# energymetter_labsi.net
KiCad netlist of a schematic drawn in EAGLE
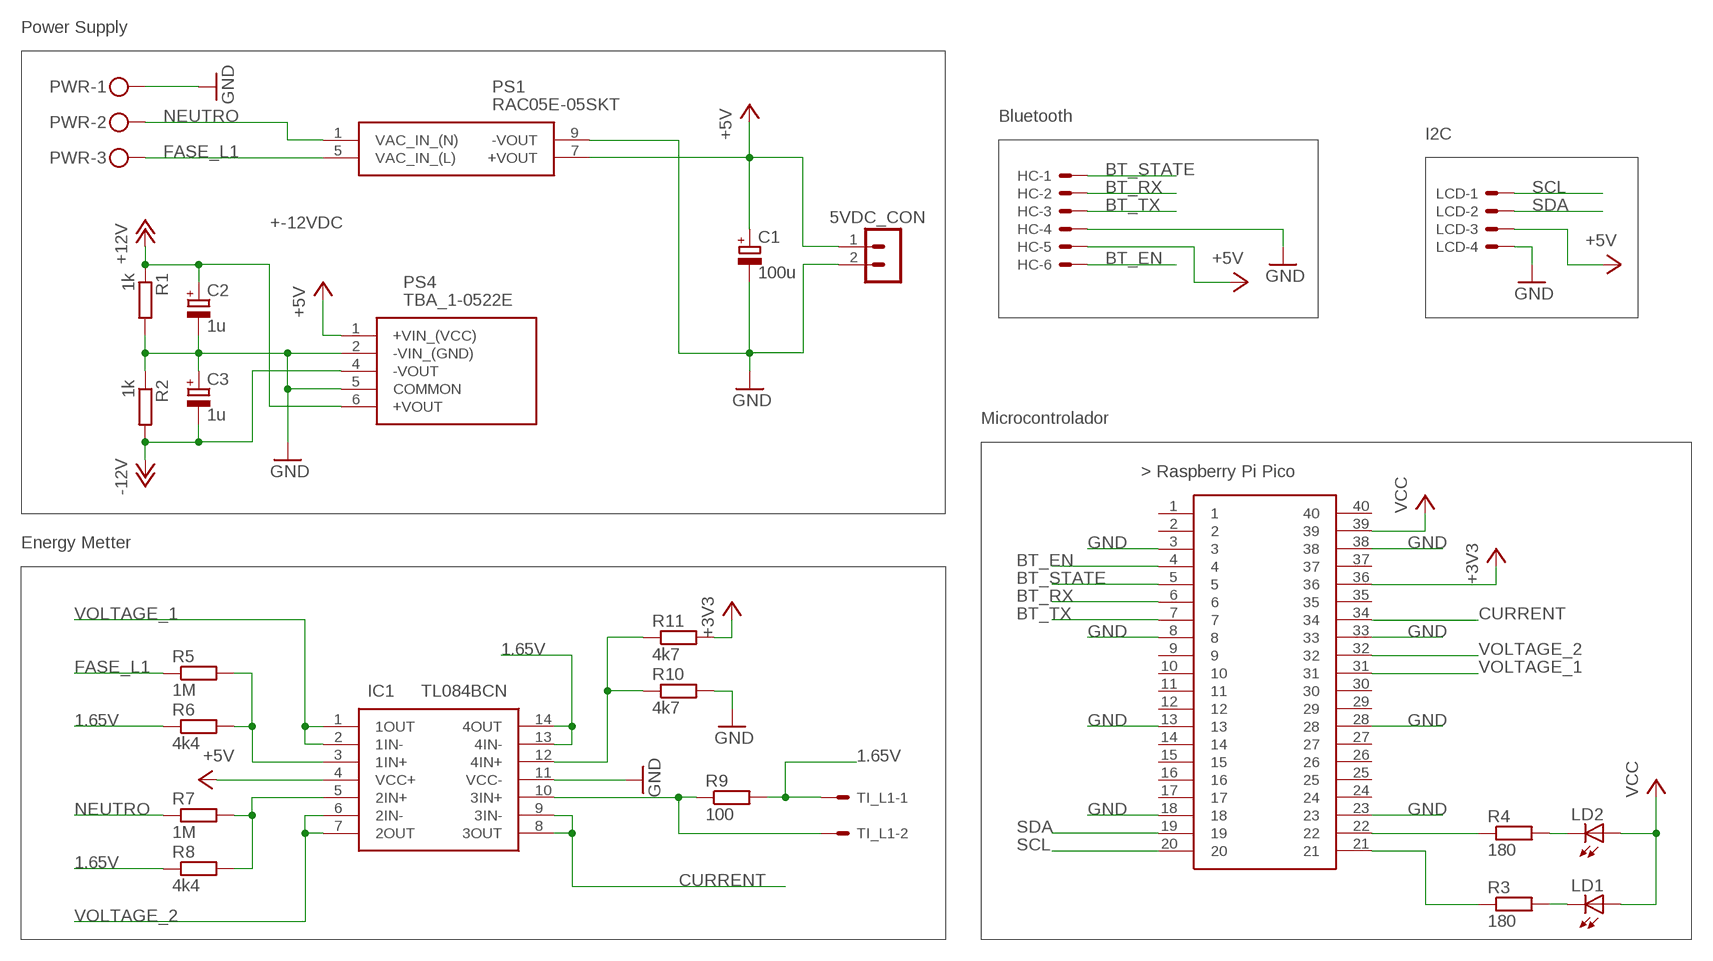
[diagram p0: schematic, sheet 1]

(export (version "E")
  (design (tool "Eeschema 10.0.6"))
  (components
    (comp (ref "5VDC_CON")
      (value "MA02-1")
      (footprint "eagle-import:MA02-1")
      (libsource (lib "eagle-import") (part "MA02-1"))
    )
    (comp (ref "C1")
      (value "100u")
      (footprint "eagle-import:E2-5")
      (libsource (lib "eagle-import") (part "CPOL-EUE2-5"))
    )
    (comp (ref "C2")
      (value "1u")
      (footprint "eagle-import:E2-5")
      (libsource (lib "eagle-import") (part "CPOL-EUE2-5"))
    )
    (comp (ref "C3")
      (value "1u")
      (footprint "eagle-import:E2-5")
      (libsource (lib "eagle-import") (part "CPOL-EUE2-5"))
    )
    (comp (ref "HC")
      (value "22-23-2061")
      (footprint "eagle-import:22-23-2061")
      (fields (field (name "MF") "MOLEX"))
      (libsource (lib "eagle-import") (part "22-23-2061"))
    )
    (comp (ref "IC1")
      (value "TL084BCN")
      (footprint "eagle-import:DIP794W53P254L1930H508Q14N")
      (fields (field (name "MOUSER_PART_NUMBER") "595-TL084BCN"))
      (libsource (lib "eagle-import") (part "TL084BCN"))
    )
    (comp (ref "LCD")
      (value "Display")
      (footprint "eagle-import:22-23-2041")
      (fields (field (name "MF") "MOLEX") (field (name "MPN") "22-23-2041"))
      (libsource (lib "eagle-import") (part "22-23-2041"))
    )
    (comp (ref "LD1")
      (value "LED5MM")
      (footprint "eagle-import:LED5MM")
      (libsource (lib "eagle-import") (part "LED5MM"))
    )
    (comp (ref "LD2")
      (value "LED5MM")
      (footprint "eagle-import:LED5MM")
      (libsource (lib "eagle-import") (part "LED5MM"))
    )
    (comp (ref "PS1")
      (value "RAC05E-05SKT")
      (footprint "eagle-import:RAC05E05SKT")
      (fields (field (name "MOUSER_PART_NUMBER") "919-RAC05E-05SKT"))
      (libsource (lib "eagle-import") (part "RAC05E-05SKT"))
    )
    (comp (ref "PS4")
      (value "TBA_1-0522E")
      (footprint "eagle-import:TBA10522E")
      (fields
        (field (name "MANUFACTURER_PART_NUMBER") "TBA 1-0522E")
        (field (name "MOUSER_PART_NUMBER") "495-TBA1-0522E")
      )
      (libsource (lib "eagle-import") (part "TBA_1-0522E"))
    )
    (comp (ref "PWR")
      (value "MKDSN1,5/3-5,08")
      (footprint "eagle-import:MKDSN1,5_3-5,08")
      (libsource (lib "eagle-import") (part "MKDSN1,5/3-5,08"))
    )
    (comp (ref "R1")
      (value "1k")
      (footprint "eagle-import:0204_7")
      (libsource (lib "eagle-import") (part "R-EU_0204/7"))
    )
    (comp (ref "R2")
      (value "1k")
      (footprint "eagle-import:0204_7")
      (libsource (lib "eagle-import") (part "R-EU_0204/7"))
    )
    (comp (ref "R3")
      (value "180")
      (footprint "eagle-import:0204_7")
      (libsource (lib "eagle-import") (part "R-EU_0204/7"))
    )
    (comp (ref "R4")
      (value "180")
      (footprint "eagle-import:0204_7")
      (libsource (lib "eagle-import") (part "R-EU_0204/7"))
    )
    (comp (ref "R5")
      (value "1M")
      (footprint "eagle-import:0204_7")
      (libsource (lib "eagle-import") (part "R-EU_0204/7"))
    )
    (comp (ref "R6")
      (value "4k4")
      (footprint "eagle-import:0204_7")
      (libsource (lib "eagle-import") (part "R-EU_0204/7"))
    )
    (comp (ref "R7")
      (value "1M")
      (footprint "eagle-import:0204_7")
      (libsource (lib "eagle-import") (part "R-EU_0204/7"))
    )
    (comp (ref "R8")
      (value "4k4")
      (footprint "eagle-import:0204_7")
      (libsource (lib "eagle-import") (part "R-EU_0204/7"))
    )
    (comp (ref "R9")
      (value "100")
      (footprint "eagle-import:0204_7")
      (libsource (lib "eagle-import") (part "R-EU_0204/7"))
    )
    (comp (ref "R10")
      (value "4k7")
      (footprint "eagle-import:0204_7")
      (libsource (lib "eagle-import") (part "R-EU_0204/7"))
    )
    (comp (ref "R11")
      (value "4k7")
      (footprint "eagle-import:0204_7")
      (libsource (lib "eagle-import") (part "R-EU_0204/7"))
    )
    (comp (ref "TI_L1")
      (value "22-23-2021")
      (footprint "eagle-import:22-23-2021")
      (fields (field (name "MF") "MOLEX"))
      (libsource (lib "eagle-import") (part "22-23-2021"))
    )
    (comp (ref "U$1")
      (value "RASPBERRY-PI-PICO_TH")
      (footprint "eagle-import:FT_RASPBERRY-PI-PICO_TH")
      (libsource (lib "eagle-import") (part "RASPBERRY-PI-PICO_TH"))
    )
  )
  (nets
    (net (code "1") (name "+3V3") (class "Default")
      (node (ref "R11") (pin "2") (pinfunction "2_2") (pintype "passive"))
      (node (ref "U$1") (pin "36") (pinfunction "36_36") (pintype "bidirectional"))
    )
    (net (code "2") (name "+5V") (class "Default")
      (node (ref "5VDC_CON") (pin "1") (pinfunction "2_1") (pintype "passive"))
      (node (ref "C1") (pin "+") (pinfunction "+_+") (pintype "passive"))
      (node (ref "HC") (pin "5") (pinfunction "S_5") (pintype "passive"))
      (node (ref "IC1") (pin "4") (pinfunction "VCC+_4") (pintype "bidirectional"))
      (node (ref "LCD") (pin "3") (pinfunction "S_3") (pintype "passive"))
      (node (ref "PS1") (pin "7") (pinfunction "+VOUT_7") (pintype "bidirectional"))
      (node (ref "PS4") (pin "1") (pinfunction "+VIN_(VCC)_1") (pintype "bidirectional"))
    )
    (net (code "3") (name "+12V") (class "Default")
      (node (ref "C2") (pin "+") (pinfunction "+_+") (pintype "passive"))
      (node (ref "PS4") (pin "6") (pinfunction "+VOUT_6") (pintype "bidirectional"))
      (node (ref "R1") (pin "1") (pinfunction "1_1") (pintype "passive"))
    )
    (net (code "4") (name "-12V") (class "Default")
      (node (ref "C3") (pin "-") (pinfunction "-_-") (pintype "passive"))
      (node (ref "PS4") (pin "4") (pinfunction "-VOUT_4") (pintype "bidirectional"))
      (node (ref "R2") (pin "2") (pinfunction "2_2") (pintype "passive"))
    )
    (net (code "5") (name "/1.65V") (class "Default")
      (node (ref "IC1") (pin "13") (pinfunction "4IN-_13") (pintype "bidirectional"))
      (node (ref "IC1") (pin "14") (pinfunction "4OUT_14") (pintype "bidirectional"))
      (node (ref "R6") (pin "1") (pinfunction "1_1") (pintype "passive"))
      (node (ref "R8") (pin "1") (pinfunction "1_1") (pintype "passive"))
      (node (ref "R9") (pin "2") (pinfunction "2_2") (pintype "passive"))
      (node (ref "TI_L1") (pin "1") (pinfunction "S_1") (pintype "passive"))
    )
    (net (code "6") (name "/BT_EN") (class "Default")
      (node (ref "HC") (pin "6") (pinfunction "S_6") (pintype "passive"))
      (node (ref "U$1") (pin "4") (pinfunction "4_4") (pintype "bidirectional"))
    )
    (net (code "7") (name "/BT_RX") (class "Default")
      (node (ref "HC") (pin "2") (pinfunction "S_2") (pintype "passive"))
      (node (ref "U$1") (pin "6") (pinfunction "6_6") (pintype "bidirectional"))
    )
    (net (code "8") (name "/BT_STATE") (class "Default")
      (node (ref "HC") (pin "1") (pinfunction "S_1") (pintype "passive"))
      (node (ref "U$1") (pin "5") (pinfunction "5_5") (pintype "bidirectional"))
    )
    (net (code "9") (name "/BT_TX") (class "Default")
      (node (ref "HC") (pin "3") (pinfunction "S_3") (pintype "passive"))
      (node (ref "U$1") (pin "7") (pinfunction "7_7") (pintype "bidirectional"))
    )
    (net (code "10") (name "/CURRENT") (class "Default")
      (node (ref "IC1") (pin "8") (pinfunction "3OUT_8") (pintype "bidirectional"))
      (node (ref "IC1") (pin "9") (pinfunction "3IN-_9") (pintype "bidirectional"))
      (node (ref "U$1") (pin "34") (pinfunction "34_34") (pintype "bidirectional"))
    )
    (net (code "11") (name "/FASE_L1") (class "Default")
      (node (ref "PS1") (pin "5") (pinfunction "VAC_IN_(L)_5") (pintype "bidirectional"))
      (node (ref "PWR") (pin "3") (pinfunction "KL_3") (pintype "passive"))
      (node (ref "R5") (pin "1") (pinfunction "1_1") (pintype "passive"))
    )
    (net (code "12") (name "/NEUTRO") (class "Default")
      (node (ref "PS1") (pin "1") (pinfunction "VAC_IN_(N)_1") (pintype "bidirectional"))
      (node (ref "PWR") (pin "2") (pinfunction "KL_2") (pintype "passive"))
      (node (ref "R7") (pin "1") (pinfunction "1_1") (pintype "passive"))
    )
    (net (code "13") (name "/SCL") (class "Default")
      (node (ref "LCD") (pin "1") (pinfunction "S_1") (pintype "passive"))
      (node (ref "U$1") (pin "20") (pinfunction "20_20") (pintype "bidirectional"))
    )
    (net (code "14") (name "/SDA") (class "Default")
      (node (ref "LCD") (pin "2") (pinfunction "S_2") (pintype "passive"))
      (node (ref "U$1") (pin "19") (pinfunction "19_19") (pintype "bidirectional"))
    )
    (net (code "15") (name "/VOLTAGE_1") (class "Default")
      (node (ref "IC1") (pin "1") (pinfunction "1OUT_1") (pintype "bidirectional"))
      (node (ref "IC1") (pin "2") (pinfunction "1IN-_2") (pintype "bidirectional"))
      (node (ref "U$1") (pin "31") (pinfunction "31_31") (pintype "bidirectional"))
    )
    (net (code "16") (name "/VOLTAGE_2") (class "Default")
      (node (ref "IC1") (pin "6") (pinfunction "2IN-_6") (pintype "bidirectional"))
      (node (ref "IC1") (pin "7") (pinfunction "2OUT_7") (pintype "bidirectional"))
      (node (ref "U$1") (pin "32") (pinfunction "32_32") (pintype "bidirectional"))
    )
    (net (code "17") (name "GND") (class "Default")
      (node (ref "5VDC_CON") (pin "2") (pinfunction "3_2") (pintype "passive"))
      (node (ref "C1") (pin "-") (pinfunction "-_-") (pintype "passive"))
      (node (ref "C2") (pin "-") (pinfunction "-_-") (pintype "passive"))
      (node (ref "C3") (pin "+") (pinfunction "+_+") (pintype "passive"))
      (node (ref "HC") (pin "4") (pinfunction "S_4") (pintype "passive"))
      (node (ref "IC1") (pin "11") (pinfunction "VCC-_11") (pintype "bidirectional"))
      (node (ref "LCD") (pin "4") (pinfunction "S_4") (pintype "passive"))
      (node (ref "PS1") (pin "9") (pinfunction "-VOUT_9") (pintype "bidirectional"))
      (node (ref "PS4") (pin "2") (pinfunction "-VIN_(GND)_2") (pintype "bidirectional"))
      (node (ref "PS4") (pin "5") (pinfunction "COMMON_5") (pintype "bidirectional"))
      (node (ref "PWR") (pin "1") (pinfunction "KL_1") (pintype "passive"))
      (node (ref "R1") (pin "2") (pinfunction "2_2") (pintype "passive"))
      (node (ref "R10") (pin "2") (pinfunction "2_2") (pintype "passive"))
      (node (ref "R2") (pin "1") (pinfunction "1_1") (pintype "passive"))
      (node (ref "U$1") (pin "13") (pinfunction "13_13") (pintype "bidirectional"))
      (node (ref "U$1") (pin "18") (pinfunction "18_18") (pintype "bidirectional"))
      (node (ref "U$1") (pin "23") (pinfunction "23_23") (pintype "bidirectional"))
      (node (ref "U$1") (pin "28") (pinfunction "28_28") (pintype "bidirectional"))
      (node (ref "U$1") (pin "3") (pinfunction "3_3") (pintype "bidirectional"))
      (node (ref "U$1") (pin "33") (pinfunction "33_33") (pintype "bidirectional"))
      (node (ref "U$1") (pin "38") (pinfunction "38_38") (pintype "bidirectional"))
      (node (ref "U$1") (pin "8") (pinfunction "8_8") (pintype "bidirectional"))
    )
    (net (code "18") (name "Net-(IC1-1IN+)") (class "Default")
      (node (ref "IC1") (pin "3") (pinfunction "1IN+_3") (pintype "bidirectional"))
      (node (ref "R5") (pin "2") (pinfunction "2_2") (pintype "passive"))
      (node (ref "R6") (pin "2") (pinfunction "2_2") (pintype "passive"))
    )
    (net (code "19") (name "Net-(IC1-2IN+)") (class "Default")
      (node (ref "IC1") (pin "5") (pinfunction "2IN+_5") (pintype "bidirectional"))
      (node (ref "R7") (pin "2") (pinfunction "2_2") (pintype "passive"))
      (node (ref "R8") (pin "2") (pinfunction "2_2") (pintype "passive"))
    )
    (net (code "20") (name "Net-(IC1-3IN+)") (class "Default")
      (node (ref "IC1") (pin "10") (pinfunction "3IN+_10") (pintype "bidirectional"))
      (node (ref "R9") (pin "1") (pinfunction "1_1") (pintype "passive"))
      (node (ref "TI_L1") (pin "2") (pinfunction "S_2") (pintype "passive"))
    )
    (net (code "21") (name "Net-(IC1-4IN+)") (class "Default")
      (node (ref "IC1") (pin "12") (pinfunction "4IN+_12") (pintype "bidirectional"))
      (node (ref "R10") (pin "1") (pinfunction "1_1") (pintype "passive"))
      (node (ref "R11") (pin "1") (pinfunction "1_1") (pintype "passive"))
    )
    (net (code "22") (name "Net-(LD1-C)") (class "Default")
      (node (ref "LD1") (pin "K") (pinfunction "C_K") (pintype "passive"))
      (node (ref "R3") (pin "2") (pinfunction "2_2") (pintype "passive"))
    )
    (net (code "23") (name "Net-(LD2-C)") (class "Default")
      (node (ref "LD2") (pin "K") (pinfunction "C_K") (pintype "passive"))
      (node (ref "R4") (pin "2") (pinfunction "2_2") (pintype "passive"))
    )
    (net (code "24") (name "Net-(R3-Pad1)") (class "Default")
      (node (ref "R3") (pin "1") (pinfunction "1_1") (pintype "passive"))
      (node (ref "U$1") (pin "21") (pinfunction "21_21") (pintype "bidirectional"))
    )
    (net (code "25") (name "Net-(R4-Pad1)") (class "Default")
      (node (ref "R4") (pin "1") (pinfunction "1_1") (pintype "passive"))
      (node (ref "U$1") (pin "22") (pinfunction "22_22") (pintype "bidirectional"))
    )
    (net (code "26") (name "VCC") (class "Default")
      (node (ref "LD1") (pin "A") (pinfunction "A_A") (pintype "passive"))
      (node (ref "LD2") (pin "A") (pinfunction "A_A") (pintype "passive"))
      (node (ref "U$1") (pin "39") (pinfunction "39_39") (pintype "bidirectional"))
    )
    (net (code "27") (name "unconnected-(U$1-Pad1)") (class "Default")
      (node (ref "U$1") (pin "1") (pinfunction "1_1") (pintype "bidirectional"))
    )
    (net (code "28") (name "unconnected-(U$1-Pad2)") (class "Default")
      (node (ref "U$1") (pin "2") (pinfunction "2_2") (pintype "bidirectional"))
    )
    (net (code "29") (name "unconnected-(U$1-Pad9)") (class "Default")
      (node (ref "U$1") (pin "9") (pinfunction "9_9") (pintype "bidirectional"))
    )
    (net (code "30") (name "unconnected-(U$1-Pad10)") (class "Default")
      (node (ref "U$1") (pin "10") (pinfunction "10_10") (pintype "bidirectional"))
    )
    (net (code "31") (name "unconnected-(U$1-Pad11)") (class "Default")
      (node (ref "U$1") (pin "11") (pinfunction "11_11") (pintype "bidirectional"))
    )
    (net (code "32") (name "unconnected-(U$1-Pad12)") (class "Default")
      (node (ref "U$1") (pin "12") (pinfunction "12_12") (pintype "bidirectional"))
    )
    (net (code "33") (name "unconnected-(U$1-Pad14)") (class "Default")
      (node (ref "U$1") (pin "14") (pinfunction "14_14") (pintype "bidirectional"))
    )
    (net (code "34") (name "unconnected-(U$1-Pad15)") (class "Default")
      (node (ref "U$1") (pin "15") (pinfunction "15_15") (pintype "bidirectional"))
    )
    (net (code "35") (name "unconnected-(U$1-Pad16)") (class "Default")
      (node (ref "U$1") (pin "16") (pinfunction "16_16") (pintype "bidirectional"))
    )
    (net (code "36") (name "unconnected-(U$1-Pad17)") (class "Default")
      (node (ref "U$1") (pin "17") (pinfunction "17_17") (pintype "bidirectional"))
    )
    (net (code "37") (name "unconnected-(U$1-Pad24)") (class "Default")
      (node (ref "U$1") (pin "24") (pinfunction "24_24") (pintype "bidirectional"))
    )
    (net (code "38") (name "unconnected-(U$1-Pad25)") (class "Default")
      (node (ref "U$1") (pin "25") (pinfunction "25_25") (pintype "bidirectional"))
    )
    (net (code "39") (name "unconnected-(U$1-Pad26)") (class "Default")
      (node (ref "U$1") (pin "26") (pinfunction "26_26") (pintype "bidirectional"))
    )
    (net (code "40") (name "unconnected-(U$1-Pad27)") (class "Default")
      (node (ref "U$1") (pin "27") (pinfunction "27_27") (pintype "bidirectional"))
    )
    (net (code "41") (name "unconnected-(U$1-Pad29)") (class "Default")
      (node (ref "U$1") (pin "29") (pinfunction "29_29") (pintype "bidirectional"))
    )
    (net (code "42") (name "unconnected-(U$1-Pad30)") (class "Default")
      (node (ref "U$1") (pin "30") (pinfunction "30_30") (pintype "bidirectional"))
    )
    (net (code "43") (name "unconnected-(U$1-Pad35)") (class "Default")
      (node (ref "U$1") (pin "35") (pinfunction "35_35") (pintype "bidirectional"))
    )
    (net (code "44") (name "unconnected-(U$1-Pad37)") (class "Default")
      (node (ref "U$1") (pin "37") (pinfunction "37_37") (pintype "bidirectional"))
    )
    (net (code "45") (name "unconnected-(U$1-Pad40)") (class "Default")
      (node (ref "U$1") (pin "40") (pinfunction "40_40") (pintype "bidirectional"))
    )
  )
)
